# ATtiny85-microcontroller.net
KiCad netlist of a schematic drawn in EAGLE
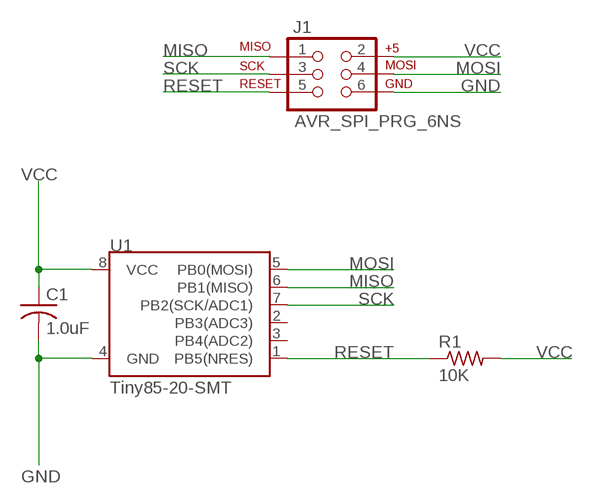
[diagram p0: schematic, sheet 1]

(export (version "E")
  (design (tool "Eeschema 10.0.6"))
  (components
    (comp (ref "C1")
      (value "1.0uF")
      (footprint "eagle-import:C1206")
      (libsource (lib "eagle-import") (part "C-USC1206"))
    )
    (comp (ref "J1")
      (value "AVR_SPI_PRG_6NS")
      (footprint "eagle-import:2X3-NS")
      (libsource (lib "eagle-import") (part "AVR_SPI_PRG_6NS"))
    )
    (comp (ref "R1")
      (value "10K")
      (footprint "eagle-import:R1206")
      (libsource (lib "eagle-import") (part "R-US_R1206"))
    )
    (comp (ref "U1")
      (value "Tiny85-20-SMT")
      (footprint "eagle-import:SO08-EIAJ")
      (libsource (lib "eagle-import") (part "ATTINY45TINY85-20-SMT"))
    )
  )
  (nets
    (net (code "1") (name "/GND") (class "Default")
      (node (ref "C1") (pin "2") (pinfunction "2_2") (pintype "passive"))
      (node (ref "J1") (pin "6") (pinfunction "6_6") (pintype "passive"))
      (node (ref "U1") (pin "4") (pinfunction "GND_4") (pintype "bidirectional"))
    )
    (net (code "2") (name "/MISO") (class "Default")
      (node (ref "J1") (pin "1") (pinfunction "1_1") (pintype "passive"))
      (node (ref "U1") (pin "6") (pinfunction "PB1(MISO)_6") (pintype "bidirectional"))
    )
    (net (code "3") (name "/MOSI") (class "Default")
      (node (ref "J1") (pin "4") (pinfunction "4_4") (pintype "passive"))
      (node (ref "U1") (pin "5") (pinfunction "PB0(MOSI)_5") (pintype "bidirectional"))
    )
    (net (code "4") (name "/RESET") (class "Default")
      (node (ref "J1") (pin "5") (pinfunction "5_5") (pintype "passive"))
      (node (ref "R1") (pin "1") (pinfunction "1_1") (pintype "passive"))
      (node (ref "U1") (pin "1") (pinfunction "PB5(NRES)_1") (pintype "bidirectional"))
    )
    (net (code "5") (name "/SCK") (class "Default")
      (node (ref "J1") (pin "3") (pinfunction "3_3") (pintype "passive"))
      (node (ref "U1") (pin "7") (pinfunction "PB2(SCK/ADC1)_7") (pintype "bidirectional"))
    )
    (net (code "6") (name "/VCC") (class "Default")
      (node (ref "C1") (pin "1") (pinfunction "1_1") (pintype "passive"))
      (node (ref "J1") (pin "2") (pinfunction "2_2") (pintype "passive"))
      (node (ref "R1") (pin "2") (pinfunction "2_2") (pintype "passive"))
      (node (ref "U1") (pin "8") (pinfunction "VCC_8") (pintype "bidirectional"))
    )
    (net (code "7") (name "unconnected-(U1-PB3(ADC3)-Pad2)") (class "Default")
      (node (ref "U1") (pin "2") (pinfunction "PB3(ADC3)_2") (pintype "bidirectional"))
    )
    (net (code "8") (name "unconnected-(U1-PB4(ADC2)-Pad3)") (class "Default")
      (node (ref "U1") (pin "3") (pinfunction "PB4(ADC2)_3") (pintype "bidirectional"))
    )
  )
)
